# Valve_master.net
KiCad netlist of a schematic drawn in EAGLE
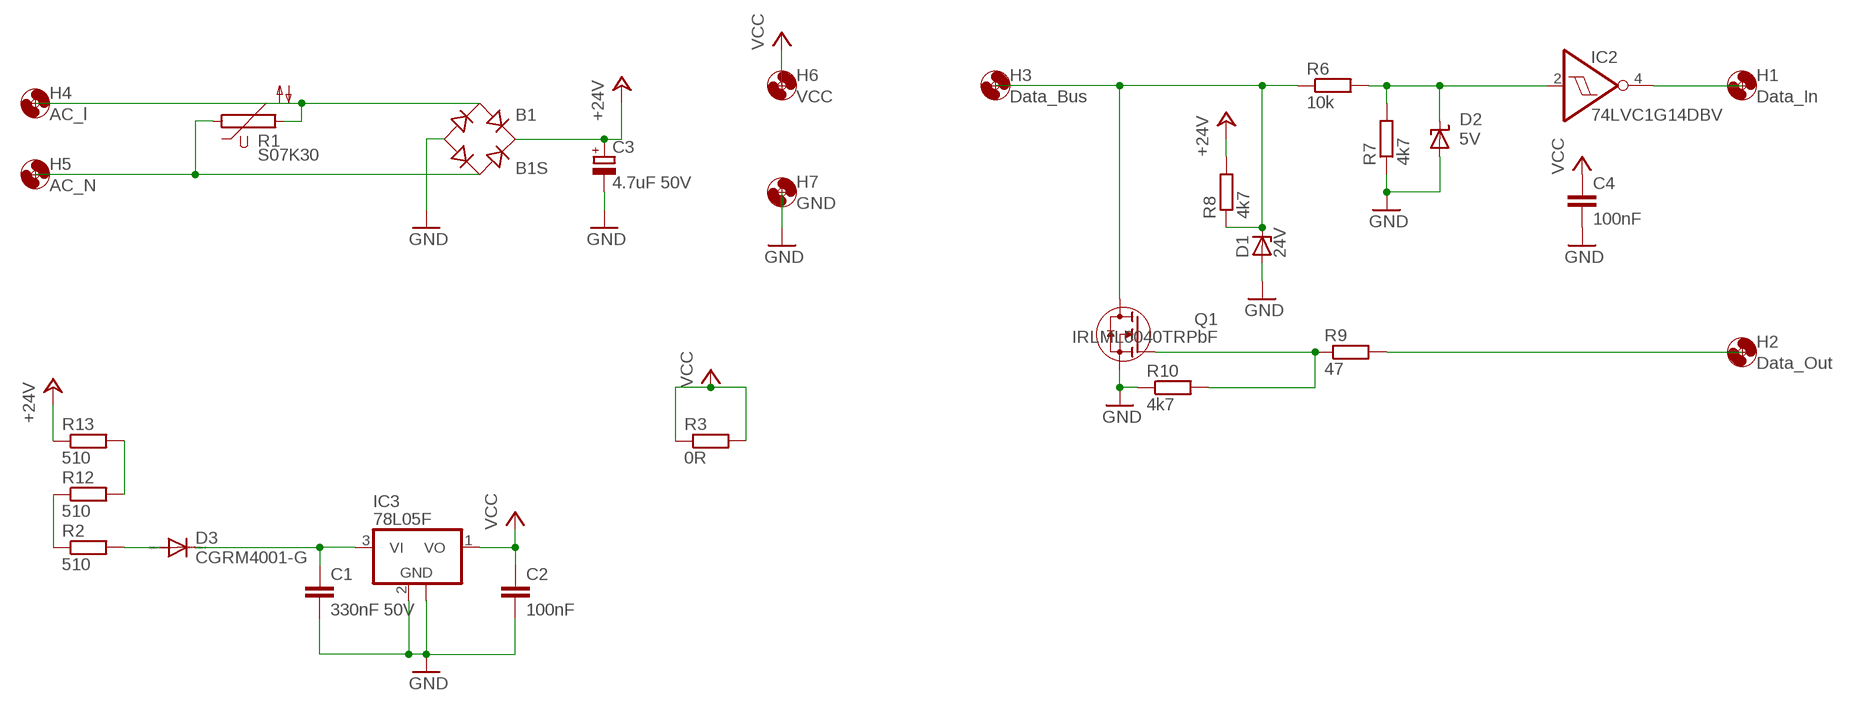
[diagram p0: schematic, sheet 1]

(export (version "E")
  (design (tool "Eeschema 10.0.6"))
  (components
    (comp (ref "B1")
      (value "B1S")
      (footprint "eagle-import:MBS")
      (libsource (lib "eagle-import") (part "BS1"))
    )
    (comp (ref "C1")
      (value "330nF 50V")
      (footprint "eagle-import:C0805K")
      (libsource (lib "eagle-import") (part "C-EUC0805K"))
    )
    (comp (ref "C2")
      (value "100nF")
      (footprint "eagle-import:C0805K")
      (libsource (lib "eagle-import") (part "C-EUC0805K"))
    )
    (comp (ref "C3")
      (value "4.7uF 50V")
      (footprint "eagle-import:D_7343-31R")
      (libsource (lib "eagle-import") (part "CPOL-EUD/7343-31R"))
    )
    (comp (ref "C4")
      (value "100nF")
      (footprint "eagle-import:0805")
      (libsource (lib "eagle-import") (part "C0805"))
    )
    (comp (ref "D1")
      (value "24V")
      (footprint "eagle-import:SOT23")
      (libsource (lib "eagle-import") (part "ZENER-DIODESOT23"))
    )
    (comp (ref "D2")
      (value "5V")
      (footprint "eagle-import:SOD123")
      (libsource (lib "eagle-import") (part "ZENER"))
    )
    (comp (ref "D3")
      (value "CGRM4001-G")
      (footprint "eagle-import:SOD-123_MINI-SMA")
      (libsource (lib "eagle-import") (part "CGRM400-G1"))
    )
    (comp (ref "H1")
      (value "Data_In")
      (footprint "eagle-import:3,2")
      (libsource (lib "eagle-import") (part "MOUNT-HOLE3.2"))
    )
    (comp (ref "H2")
      (value "Data_Out")
      (footprint "eagle-import:3,2")
      (libsource (lib "eagle-import") (part "MOUNT-HOLE3.2"))
    )
    (comp (ref "H3")
      (value "Data_Bus")
      (footprint "eagle-import:3,2")
      (libsource (lib "eagle-import") (part "MOUNT-HOLE3.2"))
    )
    (comp (ref "H4")
      (value "AC_l")
      (footprint "eagle-import:3,2")
      (libsource (lib "eagle-import") (part "MOUNT-HOLE3.2"))
    )
    (comp (ref "H5")
      (value "AC_N")
      (footprint "eagle-import:3,2")
      (libsource (lib "eagle-import") (part "MOUNT-HOLE3.2"))
    )
    (comp (ref "H6")
      (value "VCC")
      (footprint "eagle-import:3,2")
      (libsource (lib "eagle-import") (part "MOUNT-HOLE3.2"))
    )
    (comp (ref "H7")
      (value "GND")
      (footprint "eagle-import:3,2")
      (libsource (lib "eagle-import") (part "MOUNT-HOLE3.2"))
    )
    (comp (ref "IC2")
      (value "74LVC1G14DBV")
      (footprint "eagle-import:SOT23-5")
      (libsource (lib "eagle-import") (part "741G14DBVLVC"))
    )
    (comp (ref "IC3")
      (value "78L05F")
      (footprint "eagle-import:SOT89")
      (libsource (lib "eagle-import") (part "78LF05"))
    )
    (comp (ref "Q1")
      (value "IRLML0040TRPbF")
      (footprint "eagle-import:SOT-23-GSD")
      (libsource (lib "eagle-import") (part "SI2302"))
    )
    (comp (ref "R1")
      (value "S07K30")
      (footprint "eagle-import:S07K40")
      (libsource (lib "eagle-import") (part "S07K40"))
    )
    (comp (ref "R2")
      (value "510")
      (footprint "eagle-import:R2512")
      (libsource (lib "eagle-import") (part "R-EU_R2512"))
    )
    (comp (ref "R3")
      (value "0R")
      (footprint "eagle-import:0805R")
      (libsource (lib "eagle-import") (part "R0805"))
    )
    (comp (ref "R6")
      (value "10k")
      (footprint "eagle-import:R0805")
      (libsource (lib "eagle-import") (part "R-EU_R0805"))
    )
    (comp (ref "R7")
      (value "4k7")
      (footprint "eagle-import:R0805")
      (libsource (lib "eagle-import") (part "R-EU_R0805"))
    )
    (comp (ref "R8")
      (value "4k7")
      (footprint "eagle-import:R0805")
      (libsource (lib "eagle-import") (part "R-EU_R0805"))
    )
    (comp (ref "R9")
      (value "47")
      (footprint "eagle-import:R0805")
      (libsource (lib "eagle-import") (part "R-EU_R0805"))
    )
    (comp (ref "R10")
      (value "4k7")
      (footprint "eagle-import:R0805")
      (libsource (lib "eagle-import") (part "R-EU_R0805"))
    )
    (comp (ref "R12")
      (value "510")
      (footprint "eagle-import:R2512")
      (libsource (lib "eagle-import") (part "R-EU_R2512"))
    )
    (comp (ref "R13")
      (value "510")
      (footprint "eagle-import:R2512")
      (libsource (lib "eagle-import") (part "R-EU_R2512"))
    )
  )
  (nets
    (net (code "1") (name "+24V") (class "Default")
      (node (ref "B1") (pin "+") (pinfunction "+_+") (pintype "passive"))
      (node (ref "C3") (pin "+") (pinfunction "+_+") (pintype "passive"))
      (node (ref "R13") (pin "1") (pinfunction "1_1") (pintype "passive"))
      (node (ref "R8") (pin "2") (pinfunction "2_2") (pintype "passive"))
    )
    (net (code "2") (name "GND") (class "Default")
      (node (ref "B1") (pin "-") (pinfunction "-_-") (pintype "passive"))
      (node (ref "C1") (pin "2") (pinfunction "2_2") (pintype "passive"))
      (node (ref "C2") (pin "2") (pinfunction "2_2") (pintype "passive"))
      (node (ref "C3") (pin "-") (pinfunction "-_-") (pintype "passive"))
      (node (ref "C4") (pin "2") (pinfunction "2_2") (pintype "passive"))
      (node (ref "D1") (pin "1") (pinfunction "A_1") (pintype "passive"))
      (node (ref "D2") (pin "A") (pinfunction "A_A") (pintype "passive"))
      (node (ref "H7") (pin "P$1") (pinfunction "P$1_P$1") (pintype "bidirectional"))
      (node (ref "IC3") (pin "2") (pinfunction "GND_2") (pintype "passive"))
      (node (ref "IC3") (pin "2@1") (pinfunction "GND_2@1") (pintype "passive"))
      (node (ref "Q1") (pin "S") (pinfunction "S_S") (pintype "passive"))
      (node (ref "R10") (pin "1") (pinfunction "1_1") (pintype "passive"))
      (node (ref "R7") (pin "1") (pinfunction "1_1") (pintype "passive"))
    )
    (net (code "3") (name "Net-(B1-PadAC1)") (class "Default")
      (node (ref "B1") (pin "AC1") (pinfunction "AC1_AC1") (pintype "passive"))
      (node (ref "H4") (pin "P$1") (pinfunction "P$1_P$1") (pintype "bidirectional"))
      (node (ref "R1") (pin "2") (pinfunction "2_2") (pintype "passive"))
    )
    (net (code "4") (name "Net-(B1-PadAC2)") (class "Default")
      (node (ref "B1") (pin "AC2") (pinfunction "AC2_AC2") (pintype "passive"))
      (node (ref "H5") (pin "P$1") (pinfunction "P$1_P$1") (pintype "bidirectional"))
      (node (ref "R1") (pin "1") (pinfunction "1_1") (pintype "passive"))
    )
    (net (code "5") (name "Net-(D1-C)") (class "Default")
      (node (ref "D1") (pin "3") (pinfunction "C_3") (pintype "passive"))
      (node (ref "H3") (pin "P$1") (pinfunction "P$1_P$1") (pintype "bidirectional"))
      (node (ref "Q1") (pin "D") (pinfunction "D_D") (pintype "passive"))
      (node (ref "R6") (pin "1") (pinfunction "1_1") (pintype "passive"))
      (node (ref "R8") (pin "1") (pinfunction "1_1") (pintype "passive"))
    )
    (net (code "6") (name "Net-(D3-PadA)") (class "Default")
      (node (ref "D3") (pin "A") (pinfunction "A_A") (pintype "passive"))
      (node (ref "R2") (pin "2") (pinfunction "2_2") (pintype "passive"))
    )
    (net (code "7") (name "Net-(H2-PadP$1)") (class "Default")
      (node (ref "H2") (pin "P$1") (pinfunction "P$1_P$1") (pintype "bidirectional"))
      (node (ref "R9") (pin "2") (pinfunction "2_2") (pintype "passive"))
    )
    (net (code "8") (name "Net-(IC2A-I)") (class "Default")
      (node (ref "D2") (pin "C") (pinfunction "C_C") (pintype "passive"))
      (node (ref "IC2") (pin "2") (pinfunction "I_2") (pintype "input"))
      (node (ref "R6") (pin "2") (pinfunction "2_2") (pintype "passive"))
      (node (ref "R7") (pin "2") (pinfunction "2_2") (pintype "passive"))
    )
    (net (code "9") (name "Net-(IC2A-O)") (class "Default")
      (node (ref "H1") (pin "P$1") (pinfunction "P$1_P$1") (pintype "bidirectional"))
      (node (ref "IC2") (pin "4") (pinfunction "O_4") (pintype "output"))
    )
    (net (code "10") (name "Net-(IC3-VI)") (class "Default")
      (node (ref "C1") (pin "1") (pinfunction "1_1") (pintype "passive"))
      (node (ref "D3") (pin "C") (pinfunction "C_C") (pintype "passive"))
      (node (ref "IC3") (pin "3") (pinfunction "VI_3") (pintype "input"))
    )
    (net (code "11") (name "Net-(Q1-PadG)") (class "Default")
      (node (ref "Q1") (pin "G") (pinfunction "G_G") (pintype "passive"))
      (node (ref "R10") (pin "2") (pinfunction "2_2") (pintype "passive"))
      (node (ref "R9") (pin "1") (pinfunction "1_1") (pintype "passive"))
    )
    (net (code "12") (name "Net-(R12-Pad1)") (class "Default")
      (node (ref "R12") (pin "1") (pinfunction "1_1") (pintype "passive"))
      (node (ref "R2") (pin "1") (pinfunction "1_1") (pintype "passive"))
    )
    (net (code "13") (name "Net-(R12-Pad2)") (class "Default")
      (node (ref "R12") (pin "2") (pinfunction "2_2") (pintype "passive"))
      (node (ref "R13") (pin "2") (pinfunction "2_2") (pintype "passive"))
    )
    (net (code "14") (name "VCC") (class "Default")
      (node (ref "C2") (pin "1") (pinfunction "1_1") (pintype "passive"))
      (node (ref "C4") (pin "1") (pinfunction "1_1") (pintype "passive"))
      (node (ref "H6") (pin "P$1") (pinfunction "P$1_P$1") (pintype "bidirectional"))
      (node (ref "IC3") (pin "1") (pinfunction "VO_1") (pintype "passive"))
      (node (ref "R3") (pin "1") (pinfunction "1_1") (pintype "passive"))
      (node (ref "R3") (pin "2") (pinfunction "2_2") (pintype "passive"))
    )
  )
)
